# cpu.net
KiCad netlist of a schematic drawn in Altium Designer
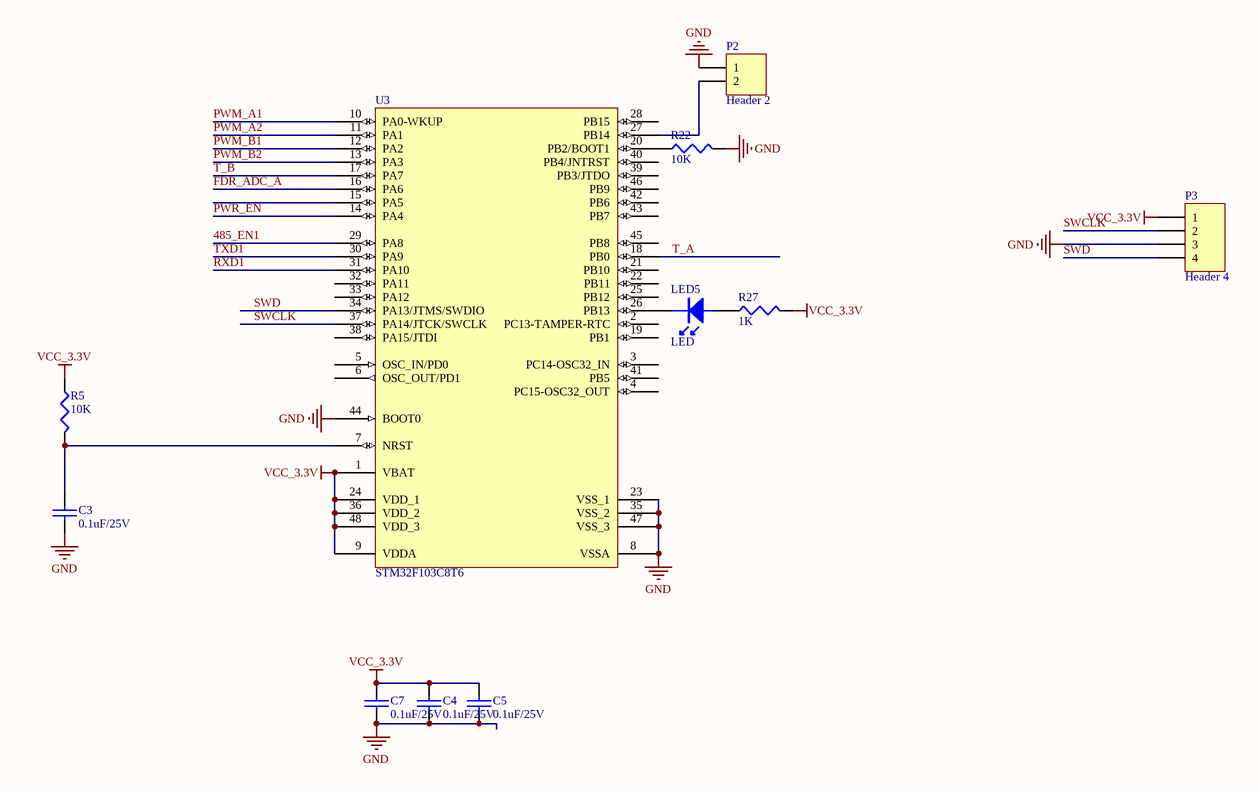
[diagram p0: cpu.SchDoc]

(export (version "E")
  (design (tool "Eeschema 10.0.6"))
  (components
    (comp (ref "C3")
      (value "0.1uF/25V")
      (footprint "0603C")
      (description "Capacitor")
      (libsource (lib "SM") (part "CAP"))
    )
    (comp (ref "C4")
      (value "0.1uF/25V")
      (footprint "0603C")
      (description "Capacitor")
      (libsource (lib "SM") (part "CAP"))
    )
    (comp (ref "C5")
      (value "0.1uF/25V")
      (footprint "0603C")
      (description "Capacitor")
      (libsource (lib "SM") (part "CAP"))
    )
    (comp (ref "C7")
      (value "0.1uF/25V")
      (footprint "0603C")
      (description "Capacitor")
      (libsource (lib "SM") (part "CAP"))
    )
    (comp (ref "LED5") (value "LED") (footprint "0603LED") (libsource (lib "我的元件库") (part "LED")))
    (comp (ref "P2")
      (value "Header 2")
      (footprint "HDR1X2")
      (description "Header, 2-Pin")
      (fields (field (name "PUBLISHER") "Altium Limited"))
      (libsource (lib "Miscellaneous Connectors") (part "Header 2"))
    )
    (comp (ref "P3")
      (value "Header 4")
      (footprint "HDR1X4")
      (description "Header, 4-Pin")
      (fields (field (name "PUBLISHER") "Altium Limited"))
      (libsource (lib "Miscellaneous Connectors") (part "Header 4"))
    )
    (comp (ref "R5")
      (value "10K")
      (footprint "0603R")
      (description "Resistor")
      (fields (field (name "PUBLISHER") "Altium Limited"))
      (libsource (lib "SM") (part "Res3"))
    )
    (comp (ref "R22")
      (value "10K")
      (footprint "0603R")
      (description "Resistor")
      (fields (field (name "PUBLISHER") "Altium Limited"))
      (libsource (lib "SM") (part "Res3"))
    )
    (comp (ref "R27")
      (value "1K")
      (footprint "0603R")
      (libsource (lib "ZWLIntegrated_Library") (part "RES1"))
    )
    (comp (ref "U3")
      (value "STM32F103C8T6")
      (footprint "TQFP-48")
      (description "STM32 ARM-based 32-bit MCU with 64 Kbytes Flash, 48-pin LQFP, Industrial Temperature")
      (fields (field (name "PUBLISHER") "Altium Limited"))
      (libsource (lib "ST Microcontroller 32-Bit STM32") (part "STM32F103C8T6"))
    )
  )
  (nets
    (net (code "1") (name "/485_EN1") (class "Default")
      (node (ref "U3") (pin "29") (pinfunction "PA8_29") (pintype "bidirectional"))
    )
    (net (code "2") (name "/FDR_ADC_A") (class "Default")
      (node (ref "U3") (pin "16") (pinfunction "PA6_16") (pintype "bidirectional"))
    )
    (net (code "3") (name "/PWM_A1") (class "Default")
      (node (ref "U3") (pin "10") (pinfunction "PA0-WKUP_10") (pintype "bidirectional"))
    )
    (net (code "4") (name "/PWM_A2") (class "Default")
      (node (ref "U3") (pin "11") (pinfunction "PA1_11") (pintype "bidirectional"))
    )
    (net (code "5") (name "/PWM_B1") (class "Default")
      (node (ref "U3") (pin "12") (pinfunction "PA2_12") (pintype "bidirectional"))
    )
    (net (code "6") (name "/PWM_B2") (class "Default")
      (node (ref "U3") (pin "13") (pinfunction "PA3_13") (pintype "bidirectional"))
    )
    (net (code "7") (name "/PWR_EN") (class "Default")
      (node (ref "U3") (pin "14") (pinfunction "PA4_14") (pintype "bidirectional"))
    )
    (net (code "8") (name "/RXD1") (class "Default")
      (node (ref "U3") (pin "31") (pinfunction "PA10_31") (pintype "bidirectional"))
    )
    (net (code "9") (name "/SWCLK") (class "Default")
      (node (ref "P3") (pin "2") (pinfunction "2_2") (pintype "passive"))
      (node (ref "U3") (pin "37") (pinfunction "PA14/JTCK/SWCLK_37") (pintype "bidirectional"))
    )
    (net (code "10") (name "/SWD") (class "Default")
      (node (ref "P3") (pin "4") (pinfunction "4_4") (pintype "passive"))
      (node (ref "U3") (pin "34") (pinfunction "PA13/JTMS/SWDIO_34") (pintype "bidirectional"))
    )
    (net (code "11") (name "/TXD1") (class "Default")
      (node (ref "U3") (pin "30") (pinfunction "PA9_30") (pintype "bidirectional"))
    )
    (net (code "12") (name "/T_A") (class "Default")
      (node (ref "U3") (pin "18") (pinfunction "PB0_18") (pintype "bidirectional"))
    )
    (net (code "13") (name "/T_B") (class "Default")
      (node (ref "U3") (pin "17") (pinfunction "PA7_17") (pintype "bidirectional"))
    )
    (net (code "14") (name "GND") (class "Default")
      (node (ref "C3") (pin "1") (pinfunction "1_1") (pintype "passive"))
      (node (ref "C4") (pin "1") (pinfunction "1_1") (pintype "passive"))
      (node (ref "C5") (pin "1") (pinfunction "1_1") (pintype "passive"))
      (node (ref "C7") (pin "1") (pinfunction "1_1") (pintype "passive"))
      (node (ref "P2") (pin "1") (pinfunction "1_1") (pintype "passive"))
      (node (ref "P3") (pin "3") (pinfunction "3_3") (pintype "passive"))
      (node (ref "R22") (pin "2") (pinfunction "2_2") (pintype "passive"))
      (node (ref "U3") (pin "23") (pinfunction "VSS_1_23") (pintype "power_in"))
      (node (ref "U3") (pin "35") (pinfunction "VSS_2_35") (pintype "power_in"))
      (node (ref "U3") (pin "44") (pinfunction "BOOT0_44") (pintype "input"))
      (node (ref "U3") (pin "47") (pinfunction "VSS_3_47") (pintype "power_in"))
      (node (ref "U3") (pin "8") (pinfunction "VSSA_8") (pintype "power_in"))
    )
    (net (code "15") (name "Net-(LED5-Pad1)") (class "Default")
      (node (ref "LED5") (pin "1") (pinfunction "1_1") (pintype "passive"))
      (node (ref "R27") (pin "1") (pinfunction "1_1") (pintype "passive"))
    )
    (net (code "16") (name "Net-(U3-NRST)") (class "Default")
      (node (ref "C3") (pin "2") (pinfunction "2_2") (pintype "passive"))
      (node (ref "R5") (pin "2") (pinfunction "2_2") (pintype "passive"))
      (node (ref "U3") (pin "7") (pinfunction "NRST_7") (pintype "bidirectional"))
    )
    (net (code "17") (name "Net-(U3-PB2{slash}BOOT1)") (class "Default")
      (node (ref "R22") (pin "1") (pinfunction "1_1") (pintype "passive"))
      (node (ref "U3") (pin "20") (pinfunction "PB2/BOOT1_20") (pintype "bidirectional"))
    )
    (net (code "18") (name "Net-(U3-PB13)") (class "Default")
      (node (ref "LED5") (pin "2") (pinfunction "2_2") (pintype "passive"))
      (node (ref "U3") (pin "26") (pinfunction "PB13_26") (pintype "bidirectional"))
    )
    (net (code "19") (name "Net-(U3-PB14)") (class "Default")
      (node (ref "P2") (pin "2") (pinfunction "2_2") (pintype "passive"))
      (node (ref "U3") (pin "27") (pinfunction "PB14_27") (pintype "bidirectional"))
    )
    (net (code "20") (name "VCC_3.3V") (class "Default")
      (node (ref "C4") (pin "2") (pinfunction "2_2") (pintype "passive"))
      (node (ref "C5") (pin "2") (pinfunction "2_2") (pintype "passive"))
      (node (ref "C7") (pin "2") (pinfunction "2_2") (pintype "passive"))
      (node (ref "P3") (pin "1") (pinfunction "1_1") (pintype "passive"))
      (node (ref "R27") (pin "2") (pinfunction "2_2") (pintype "passive"))
      (node (ref "R5") (pin "1") (pinfunction "1_1") (pintype "passive"))
      (node (ref "U3") (pin "1") (pinfunction "VBAT_1") (pintype "power_in"))
      (node (ref "U3") (pin "24") (pinfunction "VDD_1_24") (pintype "power_in"))
      (node (ref "U3") (pin "36") (pinfunction "VDD_2_36") (pintype "power_in"))
      (node (ref "U3") (pin "48") (pinfunction "VDD_3_48") (pintype "power_in"))
      (node (ref "U3") (pin "9") (pinfunction "VDDA_9") (pintype "power_in"))
    )
    (net (code "21") (name "unconnected-(U3-OSC_IN{slash}PD0-Pad5)") (class "Default")
      (node (ref "U3") (pin "5") (pinfunction "OSC_IN/PD0_5") (pintype "input"))
    )
    (net (code "22") (name "unconnected-(U3-OSC_OUT{slash}PD1-Pad6)") (class "Default")
      (node (ref "U3") (pin "6") (pinfunction "OSC_OUT/PD1_6") (pintype "output"))
    )
    (net (code "23") (name "unconnected-(U3-PA5-Pad15)") (class "Default")
      (node (ref "U3") (pin "15") (pinfunction "PA5_15") (pintype "bidirectional"))
    )
    (net (code "24") (name "unconnected-(U3-PA11-Pad32)") (class "Default")
      (node (ref "U3") (pin "32") (pinfunction "PA11_32") (pintype "bidirectional"))
    )
    (net (code "25") (name "unconnected-(U3-PA12-Pad33)") (class "Default")
      (node (ref "U3") (pin "33") (pinfunction "PA12_33") (pintype "bidirectional"))
    )
    (net (code "26") (name "unconnected-(U3-PA15{slash}JTDI-Pad38)") (class "Default")
      (node (ref "U3") (pin "38") (pinfunction "PA15/JTDI_38") (pintype "bidirectional"))
    )
    (net (code "27") (name "unconnected-(U3-PB1-Pad19)") (class "Default")
      (node (ref "U3") (pin "19") (pinfunction "PB1_19") (pintype "bidirectional"))
    )
    (net (code "28") (name "unconnected-(U3-PB3{slash}JTDO-Pad39)") (class "Default")
      (node (ref "U3") (pin "39") (pinfunction "PB3/JTDO_39") (pintype "bidirectional"))
    )
    (net (code "29") (name "unconnected-(U3-PB4{slash}JNTRST-Pad40)") (class "Default")
      (node (ref "U3") (pin "40") (pinfunction "PB4/JNTRST_40") (pintype "bidirectional"))
    )
    (net (code "30") (name "unconnected-(U3-PB5-Pad41)") (class "Default")
      (node (ref "U3") (pin "41") (pinfunction "PB5_41") (pintype "bidirectional"))
    )
    (net (code "31") (name "unconnected-(U3-PB6-Pad42)") (class "Default")
      (node (ref "U3") (pin "42") (pinfunction "PB6_42") (pintype "bidirectional"))
    )
    (net (code "32") (name "unconnected-(U3-PB7-Pad43)") (class "Default")
      (node (ref "U3") (pin "43") (pinfunction "PB7_43") (pintype "bidirectional"))
    )
    (net (code "33") (name "unconnected-(U3-PB8-Pad45)") (class "Default")
      (node (ref "U3") (pin "45") (pinfunction "PB8_45") (pintype "bidirectional"))
    )
    (net (code "34") (name "unconnected-(U3-PB9-Pad46)") (class "Default")
      (node (ref "U3") (pin "46") (pinfunction "PB9_46") (pintype "bidirectional"))
    )
    (net (code "35") (name "unconnected-(U3-PB10-Pad21)") (class "Default")
      (node (ref "U3") (pin "21") (pinfunction "PB10_21") (pintype "bidirectional"))
    )
    (net (code "36") (name "unconnected-(U3-PB11-Pad22)") (class "Default")
      (node (ref "U3") (pin "22") (pinfunction "PB11_22") (pintype "bidirectional"))
    )
    (net (code "37") (name "unconnected-(U3-PB12-Pad25)") (class "Default")
      (node (ref "U3") (pin "25") (pinfunction "PB12_25") (pintype "bidirectional"))
    )
    (net (code "38") (name "unconnected-(U3-PB15-Pad28)") (class "Default")
      (node (ref "U3") (pin "28") (pinfunction "PB15_28") (pintype "bidirectional"))
    )
    (net (code "39") (name "unconnected-(U3-PC13-TAMPER-RTC-Pad2)") (class "Default")
      (node (ref "U3") (pin "2") (pinfunction "PC13-TAMPER-RTC_2") (pintype "bidirectional"))
    )
    (net (code "40") (name "unconnected-(U3-PC14-OSC32_IN-Pad3)") (class "Default")
      (node (ref "U3") (pin "3") (pinfunction "PC14-OSC32_IN_3") (pintype "bidirectional"))
    )
    (net (code "41") (name "unconnected-(U3-PC15-OSC32_OUT-Pad4)") (class "Default")
      (node (ref "U3") (pin "4") (pinfunction "PC15-OSC32_OUT_4") (pintype "bidirectional"))
    )
  )
)
